# nm_mem.net
KiCad netlist of a schematic drawn in Altium Designer
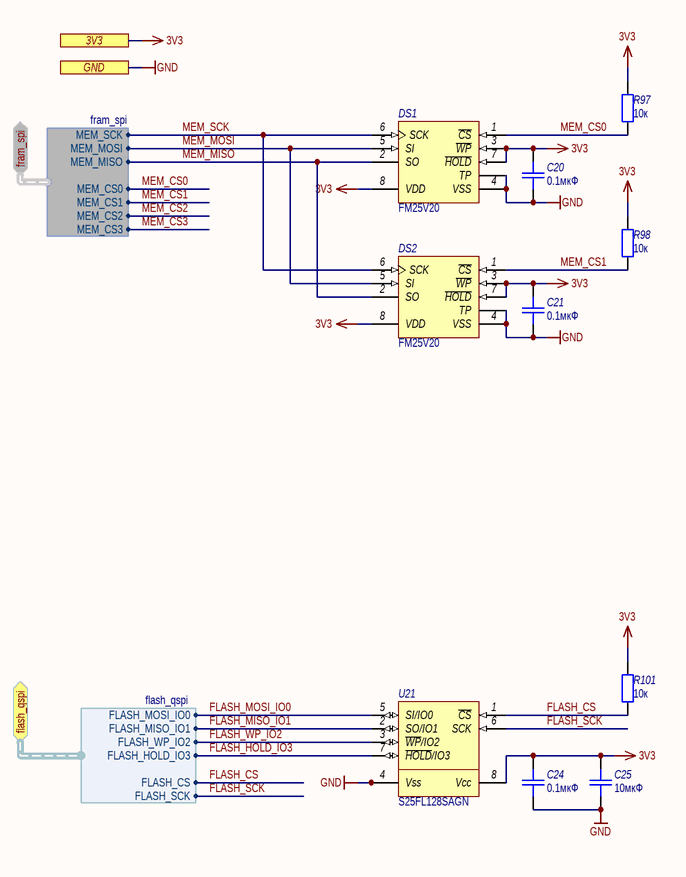
[diagram p0: nm_mem.SchDoc]

(export (version "E")
  (design (tool "Eeschema 10.0.6"))
  (components
    (comp (ref "C20")
      (value "0.1мкФ")
      (footprint "SMD_C0603")
      (description "Capacitor")
      (libsource (lib "Passive") (part "Capacitor"))
    )
    (comp (ref "C21")
      (value "0.1мкФ")
      (footprint "SMD_C0603")
      (description "Capacitor")
      (libsource (lib "Passive") (part "Capacitor"))
    )
    (comp (ref "C24")
      (value "0.1мкФ")
      (footprint "SMD_C0603")
      (description "Capacitor")
      (libsource (lib "Passive") (part "Capacitor"))
    )
    (comp (ref "C25")
      (value "10мкФ")
      (footprint "SMD_C0603")
      (description "Capacitor")
      (libsource (lib "Passive") (part "Capacitor"))
    )
    (comp (ref "DS1")
      (value "FM25V20")
      (footprint "TDFN-8_6x5")
      (description "2Mb Serial 3V FRAM Memory")
      (fields (field (name "НАИМЕНОВАНИЕ") "FM25V20"))
      (libsource (lib "Memory") (part "FM25V"))
    )
    (comp (ref "DS2")
      (value "FM25V20")
      (footprint "TDFN-8_6x5")
      (description "2Mb Serial 3V FRAM Memory")
      (fields (field (name "НАИМЕНОВАНИЕ") "FM25V20"))
      (libsource (lib "Memory") (part "FM25V"))
    )
    (comp (ref "R97")
      (value "10к")
      (footprint "SMD_0603")
      (description "Resistor")
      (libsource (lib "Passive") (part "Resistor"))
    )
    (comp (ref "R98")
      (value "10к")
      (footprint "SMD_0603")
      (description "Resistor")
      (libsource (lib "Passive") (part "Resistor"))
    )
    (comp (ref "R101")
      (value "10к")
      (footprint "SMD_0603")
      (description "Resistor")
      (libsource (lib "Passive") (part "Resistor"))
    )
    (comp (ref "U21")
      (value "S25FL128SAGN")
      (footprint "WSON-8_6x8")
      (description "Programmable NOR flash memory")
      (fields (field (name "НАИМЕНОВАНИЕ") "S25FL128SAGN"))
      (libsource (lib "Memory") (part "S25FL128SAGN"))
    )
  )
  (nets
    (net (code "3") (name "/FLASH_CS") (class "Default")
      (node (ref "R101") (pin "2") (pinfunction "2_2") (pintype "passive"))
      (node (ref "U21") (pin "1") (pinfunction "~{CS}_1") (pintype "input"))
    )
    (net (code "4") (name "/FLASH_HOLD_IO3") (class "Default")
      (node (ref "U21") (pin "7") (pinfunction "~{HOLD}/IO3_7") (pintype "bidirectional"))
    )
    (net (code "5") (name "/FLASH_MISO_IO1") (class "Default")
      (node (ref "U21") (pin "2") (pinfunction "SO/IO1_2") (pintype "bidirectional"))
    )
    (net (code "6") (name "/FLASH_MOSI_IO0") (class "Default")
      (node (ref "U21") (pin "5") (pinfunction "SI/IO0_5") (pintype "bidirectional"))
    )
    (net (code "7") (name "/FLASH_SCK") (class "Default")
      (node (ref "U21") (pin "6") (pinfunction "SCK_6") (pintype "input"))
    )
    (net (code "8") (name "/FLASH_WP_IO2") (class "Default")
      (node (ref "U21") (pin "3") (pinfunction "~{WP}/IO2_3") (pintype "bidirectional"))
    )
    (net (code "9") (name "/MEM_CS0") (class "Default")
      (node (ref "DS1") (pin "1") (pinfunction "~{CS}_1") (pintype "input"))
      (node (ref "R97") (pin "2") (pinfunction "2_2") (pintype "passive"))
    )
    (net (code "10") (name "/MEM_CS1") (class "Default")
      (node (ref "DS2") (pin "1") (pinfunction "~{CS}_1") (pintype "input"))
      (node (ref "R98") (pin "2") (pinfunction "2_2") (pintype "passive"))
    )
    (net (code "13") (name "/MEM_MISO") (class "Default")
      (node (ref "DS1") (pin "2") (pinfunction "SO_2") (pintype "tri_state"))
      (node (ref "DS2") (pin "2") (pinfunction "SO_2") (pintype "tri_state"))
    )
    (net (code "14") (name "/MEM_MOSI") (class "Default")
      (node (ref "DS1") (pin "5") (pinfunction "SI_5") (pintype "input"))
      (node (ref "DS2") (pin "5") (pinfunction "SI_5") (pintype "input"))
    )
    (net (code "15") (name "/MEM_SCK") (class "Default")
      (node (ref "DS1") (pin "6") (pinfunction "SCK_6") (pintype "input"))
      (node (ref "DS2") (pin "6") (pinfunction "SCK_6") (pintype "input"))
    )
    (net (code "18") (name "3V3") (class "Default")
      (node (ref "C20") (pin "2") (pinfunction "2_2") (pintype "passive"))
      (node (ref "C21") (pin "2") (pinfunction "2_2") (pintype "passive"))
      (node (ref "C24") (pin "2") (pinfunction "2_2") (pintype "passive"))
      (node (ref "C25") (pin "2") (pinfunction "2_2") (pintype "passive"))
      (node (ref "DS1") (pin "3") (pinfunction "~{WP}_3") (pintype "input"))
      (node (ref "DS1") (pin "7") (pinfunction "~{HOLD}_7") (pintype "input"))
      (node (ref "DS1") (pin "8") (pinfunction "VDD_8") (pintype "power_in"))
      (node (ref "DS2") (pin "3") (pinfunction "~{WP}_3") (pintype "input"))
      (node (ref "DS2") (pin "7") (pinfunction "~{HOLD}_7") (pintype "input"))
      (node (ref "DS2") (pin "8") (pinfunction "VDD_8") (pintype "power_in"))
      (node (ref "R101") (pin "1") (pinfunction "1_1") (pintype "passive"))
      (node (ref "R97") (pin "1") (pinfunction "1_1") (pintype "passive"))
      (node (ref "R98") (pin "1") (pinfunction "1_1") (pintype "passive"))
      (node (ref "U21") (pin "8") (pinfunction "Vcc_8") (pintype "power_in"))
    )
    (net (code "19") (name "GND") (class "Default")
      (node (ref "C20") (pin "1") (pinfunction "1_1") (pintype "passive"))
      (node (ref "C21") (pin "1") (pinfunction "1_1") (pintype "passive"))
      (node (ref "C24") (pin "1") (pinfunction "1_1") (pintype "passive"))
      (node (ref "C25") (pin "1") (pinfunction "1_1") (pintype "passive"))
      (node (ref "DS1") (pin "4") (pinfunction "VSS_4") (pintype "power_in"))
      (node (ref "DS1") (pin "TP") (pinfunction "TP_TP") (pintype "power_in"))
      (node (ref "DS2") (pin "4") (pinfunction "VSS_4") (pintype "power_in"))
      (node (ref "DS2") (pin "TP") (pinfunction "TP_TP") (pintype "power_in"))
      (node (ref "U21") (pin "4") (pinfunction "Vss_4") (pintype "power_in"))
      (node (ref "U21") (pin "9") (pinfunction "TP_9") (pintype "power_in"))
    )
  )
)
